# untitled.net
KiCad netlist of a schematic drawn in EAGLE
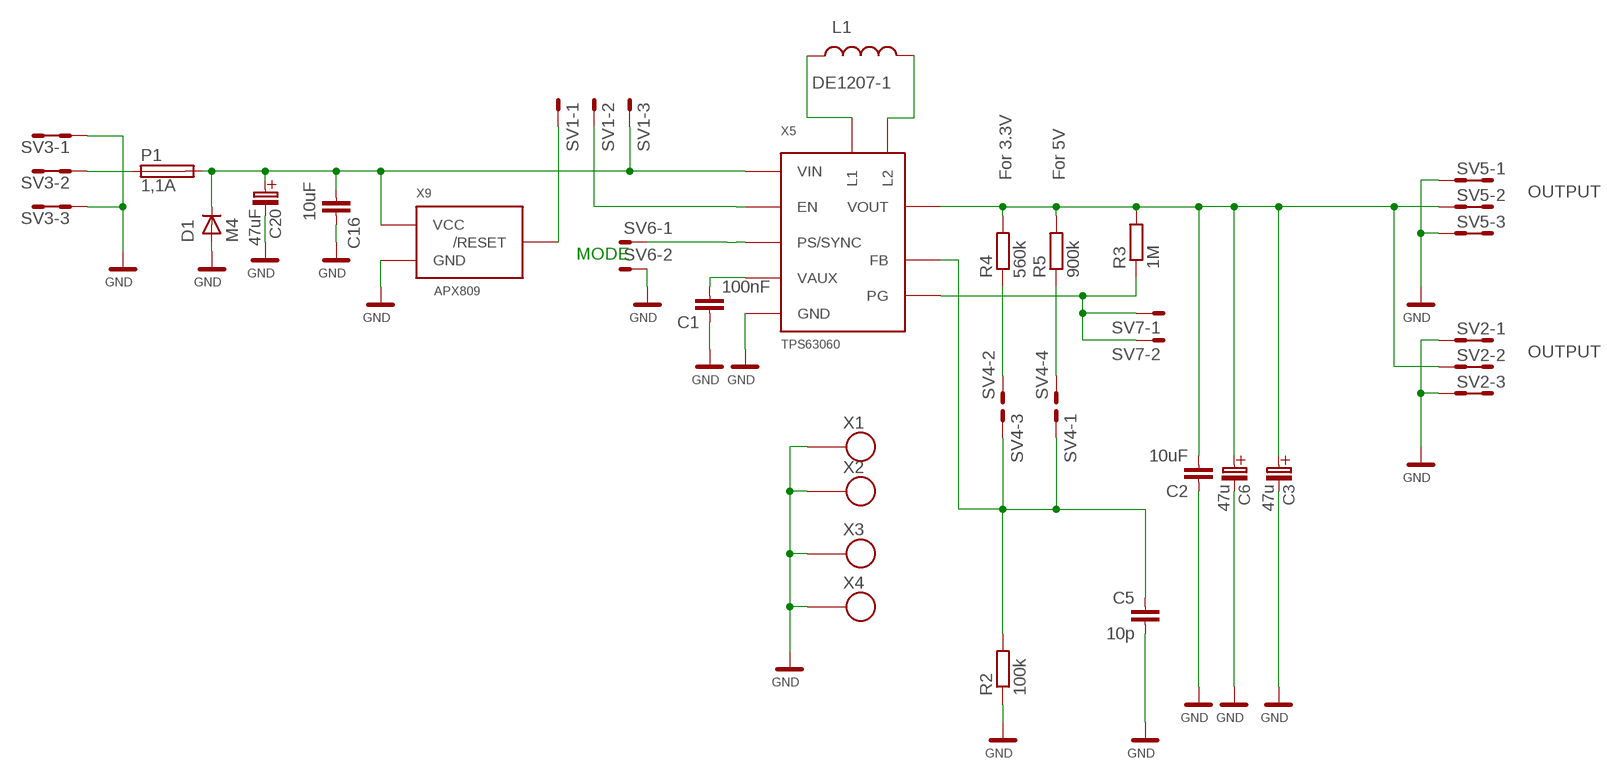
[diagram p0: schematic, sheet 1]

(export (version "E")
  (design (tool "Eeschema 10.0.6"))
  (components
    (comp (ref "C1")
      (value "100nF")
      (footprint "eagle-import:C0805")
      (libsource (lib "eagle-import") (part "C0805"))
    )
    (comp (ref "C2")
      (value "10uF")
      (footprint "eagle-import:C0805")
      (libsource (lib "eagle-import") (part "C0805"))
    )
    (comp (ref "C3") (value "47u") (footprint "eagle-import:C") (libsource (lib "eagle-import") (part "C")))
    (comp (ref "C5")
      (value "10p")
      (footprint "eagle-import:C0805")
      (libsource (lib "eagle-import") (part "C0805"))
    )
    (comp (ref "C6") (value "47u") (footprint "eagle-import:C") (libsource (lib "eagle-import") (part "C")))
    (comp (ref "C16")
      (value "10uF")
      (footprint "eagle-import:C0805")
      (libsource (lib "eagle-import") (part "C0805"))
    )
    (comp (ref "C20") (value "47uF") (footprint "eagle-import:C") (libsource (lib "eagle-import") (part "C")))
    (comp (ref "D1")
      (value "M4")
      (footprint "eagle-import:SMA")
      (libsource (lib "eagle-import") (part "D-OB.SMA"))
    )
    (comp (ref "L1")
      (value "DE1207-1")
      (footprint "eagle-import:DE1205-10")
      (libsource (lib "eagle-import") (part "DE1205-10"))
    )
    (comp (ref "P1")
      (value "1,1A")
      (footprint "eagle-import:1812")
      (libsource (lib "eagle-import") (part "POJISTKA_1812"))
    )
    (comp (ref "R2")
      (value "100k")
      (footprint "eagle-import:0805")
      (libsource (lib "eagle-import") (part "R0805"))
    )
    (comp (ref "R3")
      (value "1M")
      (footprint "eagle-import:0805")
      (libsource (lib "eagle-import") (part "R0805"))
    )
    (comp (ref "R4")
      (value "560k")
      (footprint "eagle-import:0805")
      (libsource (lib "eagle-import") (part "R0805"))
    )
    (comp (ref "R5")
      (value "900k")
      (footprint "eagle-import:0805")
      (libsource (lib "eagle-import") (part "R0805"))
    )
    (comp (ref "SV1")
      (value "MA03-1")
      (footprint "eagle-import:MA03-1")
      (libsource (lib "eagle-import") (part "MA03-1"))
    )
    (comp (ref "SV2")
      (value "MA03-2")
      (footprint "eagle-import:MA03-2")
      (libsource (lib "eagle-import") (part "MA03-2"))
    )
    (comp (ref "SV3")
      (value "MA03-2")
      (footprint "eagle-import:MA03-2")
      (libsource (lib "eagle-import") (part "MA03-2"))
    )
    (comp (ref "SV4")
      (value "MA02-3")
      (footprint "eagle-import:MA02-2")
      (libsource (lib "eagle-import") (part "MA02-3"))
    )
    (comp (ref "SV5")
      (value "MA03-2")
      (footprint "eagle-import:MA03-2")
      (libsource (lib "eagle-import") (part "MA03-2"))
    )
    (comp (ref "SV6")
      (value "MA02-1")
      (footprint "eagle-import:MA02-1")
      (libsource (lib "eagle-import") (part "MA02-1"))
    )
    (comp (ref "SV7")
      (value "MA02-1")
      (footprint "eagle-import:MA02-1")
      (libsource (lib "eagle-import") (part "MA02-1"))
    )
    (comp (ref "X1")
      (value "SROUB3M")
      (footprint "eagle-import:SROUB3M")
      (libsource (lib "eagle-import") (part "SROUB3M"))
    )
    (comp (ref "X2")
      (value "SROUB3M")
      (footprint "eagle-import:SROUB3M")
      (libsource (lib "eagle-import") (part "SROUB3M"))
    )
    (comp (ref "X3")
      (value "SROUB3M")
      (footprint "eagle-import:SROUB3M")
      (libsource (lib "eagle-import") (part "SROUB3M"))
    )
    (comp (ref "X4")
      (value "SROUB3M")
      (footprint "eagle-import:SROUB3M")
      (libsource (lib "eagle-import") (part "SROUB3M"))
    )
    (comp (ref "X5")
      (value "TPS63060")
      (footprint "eagle-import:SON10")
      (libsource (lib "eagle-import") (part "TPS63060"))
    )
    (comp (ref "X9")
      (value "APX809")
      (footprint "eagle-import:SOT23")
      (libsource (lib "eagle-import") (part "APX809-26SA"))
    )
  )
  (nets
    (net (code "1") (name "GND") (class "Default")
      (node (ref "C1") (pin "1") (pinfunction "1_1") (pintype "passive"))
      (node (ref "C16") (pin "1") (pinfunction "1_1") (pintype "passive"))
      (node (ref "C2") (pin "1") (pinfunction "1_1") (pintype "passive"))
      (node (ref "C20") (pin "-") (pinfunction "C_EL-_-") (pintype "passive"))
      (node (ref "C3") (pin "-") (pinfunction "C_EL-_-") (pintype "passive"))
      (node (ref "C5") (pin "2") (pinfunction "2_2") (pintype "passive"))
      (node (ref "C6") (pin "-") (pinfunction "C_EL-_-") (pintype "passive"))
      (node (ref "D1") (pin "A") (pinfunction "A_A") (pintype "passive"))
      (node (ref "R2") (pin "1") (pinfunction "1_1") (pintype "passive"))
      (node (ref "SV2") (pin "1") (pinfunction "K_1") (pintype "passive"))
      (node (ref "SV2") (pin "2") (pinfunction "K_2") (pintype "passive"))
      (node (ref "SV2") (pin "5") (pinfunction "K_5") (pintype "passive"))
      (node (ref "SV2") (pin "6") (pinfunction "K_6") (pintype "passive"))
      (node (ref "SV3") (pin "1") (pinfunction "K_1") (pintype "passive"))
      (node (ref "SV3") (pin "2") (pinfunction "K_2") (pintype "passive"))
      (node (ref "SV3") (pin "5") (pinfunction "K_5") (pintype "passive"))
      (node (ref "SV3") (pin "6") (pinfunction "K_6") (pintype "passive"))
      (node (ref "SV5") (pin "1") (pinfunction "K_1") (pintype "passive"))
      (node (ref "SV5") (pin "2") (pinfunction "K_2") (pintype "passive"))
      (node (ref "SV5") (pin "5") (pinfunction "K_5") (pintype "passive"))
      (node (ref "SV5") (pin "6") (pinfunction "K_6") (pintype "passive"))
      (node (ref "SV6") (pin "2") (pinfunction "P$1_2") (pintype "passive"))
      (node (ref "X1") (pin "P$1") (pinfunction "P$1_P$1") (pintype "bidirectional"))
      (node (ref "X2") (pin "P$1") (pinfunction "P$1_P$1") (pintype "bidirectional"))
      (node (ref "X3") (pin "P$1") (pinfunction "P$1_P$1") (pintype "bidirectional"))
      (node (ref "X4") (pin "P$1") (pinfunction "P$1_P$1") (pintype "bidirectional"))
      (node (ref "X5") (pin "11") (pinfunction "GND_11") (pintype "passive"))
      (node (ref "X5") (pin "12") (pinfunction "GND_12") (pintype "passive"))
      (node (ref "X5") (pin "13") (pinfunction "GND_13") (pintype "passive"))
      (node (ref "X5") (pin "14") (pinfunction "GND_14") (pintype "passive"))
      (node (ref "X5") (pin "15") (pinfunction "GND_15") (pintype "passive"))
      (node (ref "X5") (pin "16") (pinfunction "GND_16") (pintype "passive"))
      (node (ref "X5") (pin "17") (pinfunction "GND_17") (pintype "passive"))
      (node (ref "X5") (pin "18") (pinfunction "GND_18") (pintype "passive"))
      (node (ref "X5") (pin "19") (pinfunction "GND_19") (pintype "passive"))
      (node (ref "X5") (pin "7") (pinfunction "GND_7") (pintype "passive"))
      (node (ref "X5") (pin "P$1") (pinfunction "GND_P$1") (pintype "passive"))
      (node (ref "X5") (pin "P$2") (pinfunction "GND_P$2") (pintype "passive"))
      (node (ref "X5") (pin "P$3") (pinfunction "GND_P$3") (pintype "passive"))
      (node (ref "X5") (pin "P$4") (pinfunction "GND_P$4") (pintype "passive"))
      (node (ref "X5") (pin "P$5") (pinfunction "GND_P$5") (pintype "passive"))
      (node (ref "X9") (pin "1") (pinfunction "GND_1") (pintype "passive"))
    )
    (net (code "2") (name "Net-(C3-C_EL+)") (class "Default")
      (node (ref "C2") (pin "2") (pinfunction "2_2") (pintype "passive"))
      (node (ref "C3") (pin "+") (pinfunction "C_EL+_+") (pintype "passive"))
      (node (ref "C6") (pin "+") (pinfunction "C_EL+_+") (pintype "passive"))
      (node (ref "R3") (pin "2") (pinfunction "2_2") (pintype "passive"))
      (node (ref "R4") (pin "2") (pinfunction "2_2") (pintype "passive"))
      (node (ref "R5") (pin "2") (pinfunction "2_2") (pintype "passive"))
      (node (ref "SV2") (pin "3") (pinfunction "K_3") (pintype "passive"))
      (node (ref "SV2") (pin "4") (pinfunction "K_4") (pintype "passive"))
      (node (ref "SV5") (pin "3") (pinfunction "K_3") (pintype "passive"))
      (node (ref "SV5") (pin "4") (pinfunction "K_4") (pintype "passive"))
      (node (ref "X5") (pin "9") (pinfunction "VOUT_9") (pintype "output"))
    )
    (net (code "3") (name "Net-(C20-C_EL+)") (class "Default")
      (node (ref "C16") (pin "2") (pinfunction "2_2") (pintype "passive"))
      (node (ref "C20") (pin "+") (pinfunction "C_EL+_+") (pintype "passive"))
      (node (ref "D1") (pin "K") (pinfunction "C_K") (pintype "passive"))
      (node (ref "P1") (pin "2") (pinfunction "2_2") (pintype "passive"))
      (node (ref "SV1") (pin "3") (pinfunction "P$1_3") (pintype "passive"))
      (node (ref "X5") (pin "2") (pinfunction "VIN_2") (pintype "input"))
      (node (ref "X9") (pin "3") (pinfunction "VCC_3") (pintype "input"))
    )
    (net (code "4") (name "Net-(L1-1)") (class "Default")
      (node (ref "L1") (pin "P$1") (pinfunction "1_P$1") (pintype "passive"))
      (node (ref "X5") (pin "1") (pinfunction "L1_1") (pintype "passive"))
    )
    (net (code "5") (name "Net-(L1-2)") (class "Default")
      (node (ref "L1") (pin "P$2") (pinfunction "2_P$2") (pintype "passive"))
      (node (ref "X5") (pin "10") (pinfunction "L2_10") (pintype "passive"))
    )
    (net (code "6") (name "Net-(P1-Pad1)") (class "Default")
      (node (ref "P1") (pin "1") (pinfunction "1_1") (pintype "passive"))
      (node (ref "SV3") (pin "3") (pinfunction "K_3") (pintype "passive"))
      (node (ref "SV3") (pin "4") (pinfunction "K_4") (pintype "passive"))
    )
    (net (code "7") (name "Net-(SV1A-P$1)") (class "Default")
      (node (ref "SV1") (pin "1") (pinfunction "P$1_1") (pintype "passive"))
      (node (ref "X9") (pin "2") (pinfunction "/RESET_2") (pintype "passive"))
    )
    (net (code "8") (name "Net-(SV1B-P$1)") (class "Default")
      (node (ref "SV1") (pin "2") (pinfunction "P$1_2") (pintype "passive"))
      (node (ref "X5") (pin "3") (pinfunction "EN_3") (pintype "input"))
    )
    (net (code "9") (name "Net-(SV4A-P$1)") (class "Default")
      (node (ref "C5") (pin "1") (pinfunction "1_1") (pintype "passive"))
      (node (ref "R2") (pin "2") (pinfunction "2_2") (pintype "passive"))
      (node (ref "SV4") (pin "1") (pinfunction "P$1_1") (pintype "passive"))
      (node (ref "SV4") (pin "3") (pinfunction "P$1_3") (pintype "passive"))
      (node (ref "X5") (pin "8") (pinfunction "FB_8") (pintype "input"))
    )
    (net (code "10") (name "Net-(SV4B-P$1)") (class "Default")
      (node (ref "R4") (pin "1") (pinfunction "1_1") (pintype "passive"))
      (node (ref "SV4") (pin "2") (pinfunction "P$1_2") (pintype "passive"))
    )
    (net (code "11") (name "Net-(SV4D-P$1)") (class "Default")
      (node (ref "R5") (pin "1") (pinfunction "1_1") (pintype "passive"))
      (node (ref "SV4") (pin "4") (pinfunction "P$1_4") (pintype "passive"))
    )
    (net (code "12") (name "Net-(SV6A-P$1)") (class "Default")
      (node (ref "SV6") (pin "1") (pinfunction "P$1_1") (pintype "passive"))
      (node (ref "X5") (pin "4") (pinfunction "PS/SYNC_4") (pintype "input"))
    )
    (net (code "13") (name "Net-(SV7A-P$1)") (class "Default")
      (node (ref "R3") (pin "1") (pinfunction "1_1") (pintype "passive"))
      (node (ref "SV7") (pin "1") (pinfunction "P$1_1") (pintype "passive"))
      (node (ref "SV7") (pin "2") (pinfunction "P$1_2") (pintype "passive"))
      (node (ref "X5") (pin "5") (pinfunction "PG_5") (pintype "input"))
    )
    (net (code "14") (name "Net-(X5-VAUX)") (class "Default")
      (node (ref "C1") (pin "2") (pinfunction "2_2") (pintype "passive"))
      (node (ref "X5") (pin "6") (pinfunction "VAUX_6") (pintype "input"))
    )
  )
)
